# Digital_Clock_v2.net
KiCad netlist of a schematic drawn in EAGLE
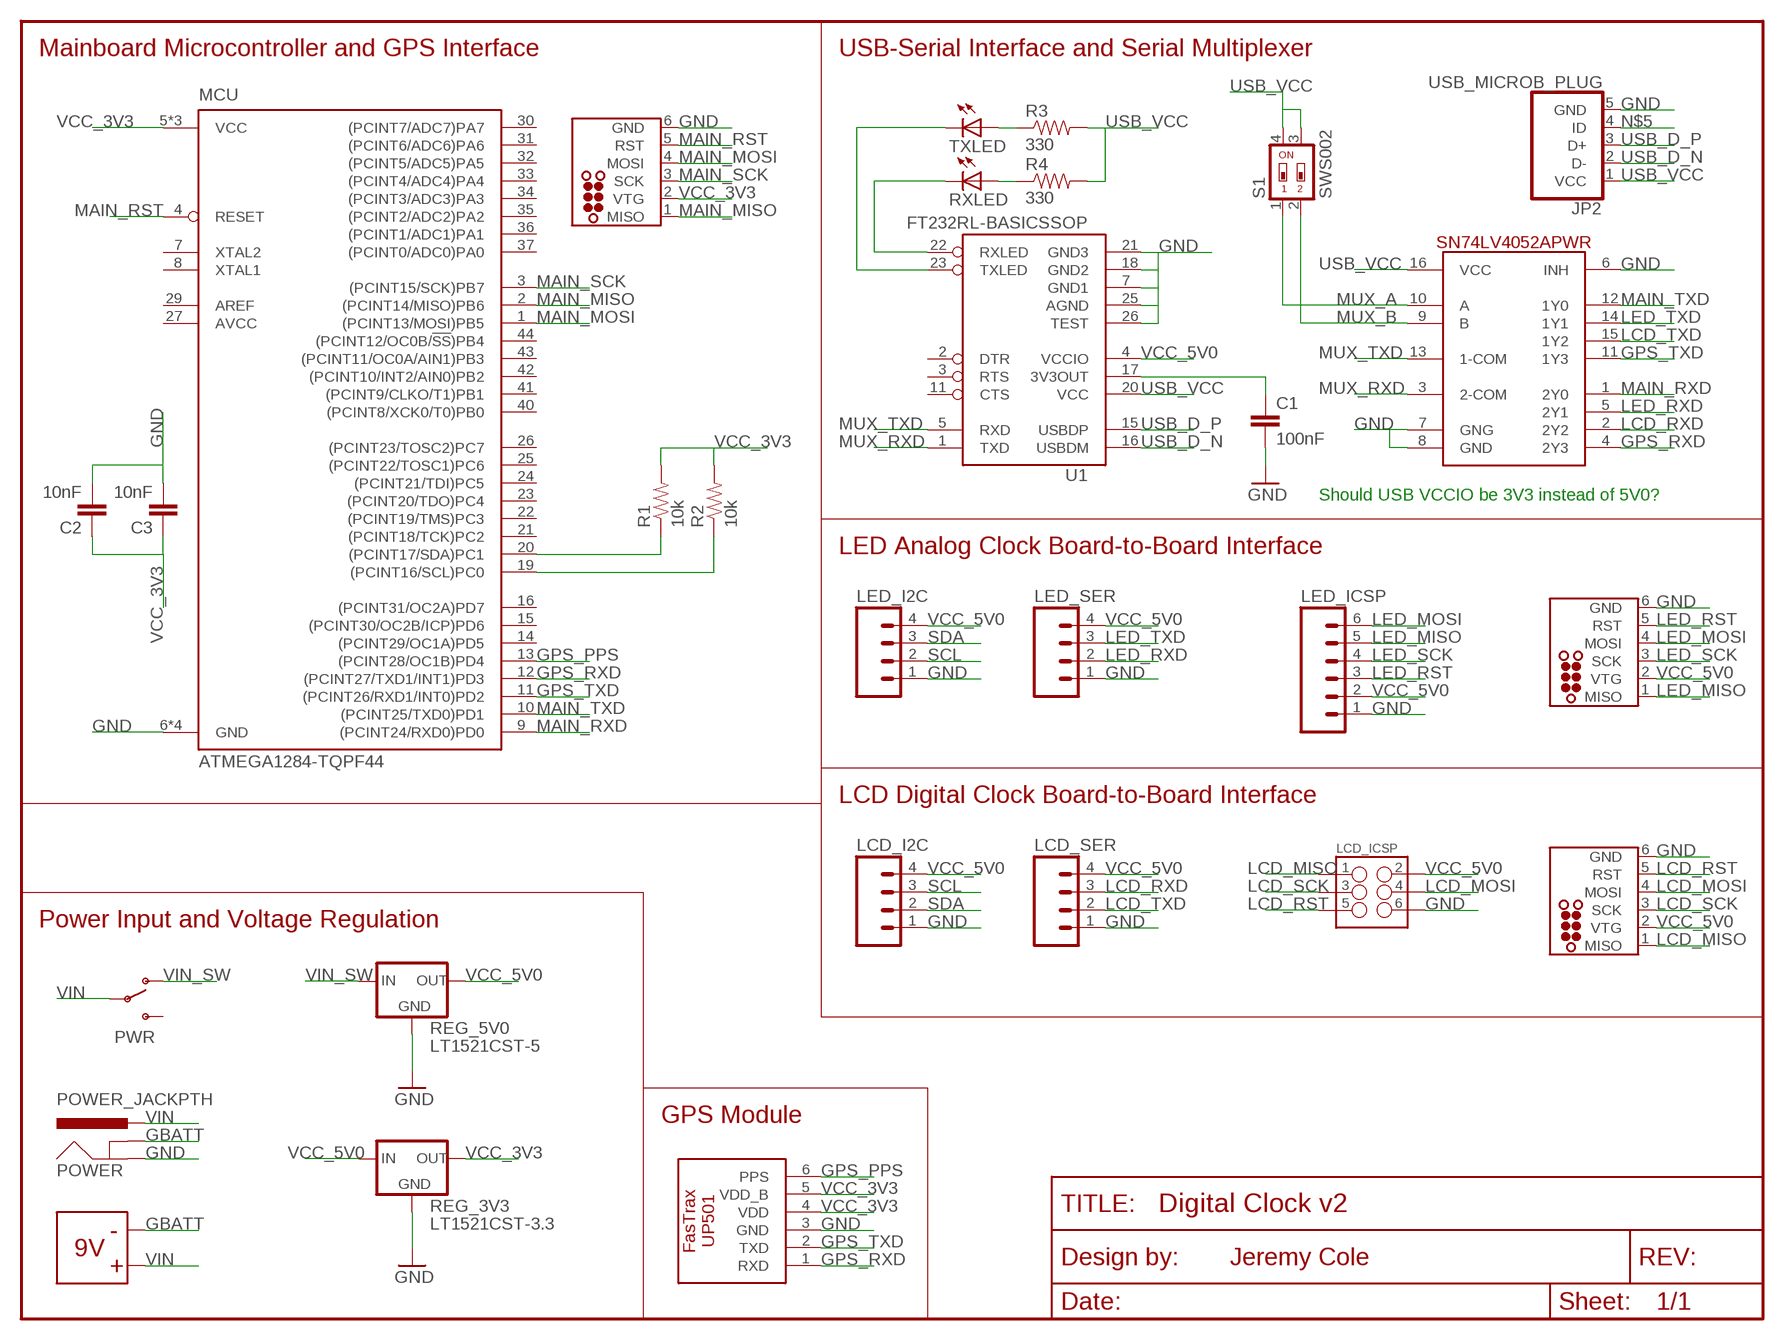
[diagram p0: schematic, sheet 1]

(export (version "E")
  (design (tool "Eeschema 10.0.6"))
  (components
    (comp (ref "9V_BATTERY")
      (value "BATTERY-BH9VGLUE")
      (footprint "eagle-import:BATTERY-BH9V-GLUE")
      (libsource (lib "eagle-import") (part "BATTERY-BH9VGLUE"))
    )
    (comp (ref "C1")
      (value "100nF")
      (footprint "eagle-import:0603-CAP")
      (libsource (lib "eagle-import") (part "CAP-0603"))
    )
    (comp (ref "C2")
      (value "10nF")
      (footprint "eagle-import:0603-CAP")
      (libsource (lib "eagle-import") (part "CAP-0603"))
    )
    (comp (ref "C3")
      (value "10nF")
      (footprint "eagle-import:0603-CAP")
      (libsource (lib "eagle-import") (part "CAP-0603"))
    )
    (comp (ref "FRAME1")
      (value "FRAME-LETTERNO_PACKAGE")
      (footprint "eagle-import:DUMMY")
      (fields (field (name "DESIGNER") "Nobody"))
      (libsource (lib "eagle-import") (part "FRAME-LETTERNO_PACKAGE"))
    )
    (comp (ref "GPS_ICSP_TC")
      (value "TC2030-AVR-NL")
      (footprint "eagle-import:TC2030-NL")
      (libsource (lib "eagle-import") (part "TC2030-AVR-NL"))
    )
    (comp (ref "JP2")
      (value "USB_MICROB_PLUG")
      (footprint "eagle-import:USB_MICRO_B_TYCO")
      (libsource (lib "eagle-import") (part "USB_MICROB_PLUG"))
    )
    (comp (ref "LCD_I2C")
      (value "M04LONGPADS")
      (footprint "eagle-import:1X04_LONGPADS")
      (libsource (lib "eagle-import") (part "M04LONGPADS"))
    )
    (comp (ref "LCD_ICSP")
      (value "M03X22X3_SILK_MALE_PTH")
      (footprint "eagle-import:2X3")
      (libsource (lib "eagle-import") (part "M03X22X3_SILK_MALE_PTH"))
    )
    (comp (ref "LCD_ICSP_TC")
      (value "TC2030-AVR-NL")
      (footprint "eagle-import:TC2030-NL")
      (libsource (lib "eagle-import") (part "TC2030-AVR-NL"))
    )
    (comp (ref "LCD_SER")
      (value "M04LONGPADS")
      (footprint "eagle-import:1X04_LONGPADS")
      (libsource (lib "eagle-import") (part "M04LONGPADS"))
    )
    (comp (ref "LED_I2C")
      (value "M04LONGPADS")
      (footprint "eagle-import:1X04_LONGPADS")
      (libsource (lib "eagle-import") (part "M04LONGPADS"))
    )
    (comp (ref "LED_ICSP")
      (value "M06LONGPADS")
      (footprint "eagle-import:1X06_LONGPADS")
      (libsource (lib "eagle-import") (part "M06LONGPADS"))
    )
    (comp (ref "LED_ICSP_TC")
      (value "TC2030-AVR-NL")
      (footprint "eagle-import:TC2030-NL")
      (libsource (lib "eagle-import") (part "TC2030-AVR-NL"))
    )
    (comp (ref "LED_SER")
      (value "M04LONGPADS")
      (footprint "eagle-import:1X04_LONGPADS")
      (libsource (lib "eagle-import") (part "M04LONGPADS"))
    )
    (comp (ref "MCU")
      (value "ATMEGA1284-TQPF44")
      (footprint "eagle-import:TQFP44")
      (libsource (lib "eagle-import") (part "ATMEGA1284-TQPF44"))
    )
    (comp (ref "POWER")
      (value "POWER_JACKPTH")
      (footprint "eagle-import:POWER_JACK_PTH")
      (libsource (lib "eagle-import") (part "POWER_JACKPTH"))
    )
    (comp (ref "PWR")
      (value "SWITCH-SPSTPTH")
      (footprint "eagle-import:SWITCH-SPDT")
      (libsource (lib "eagle-import") (part "SWITCH-SPSTPTH"))
    )
    (comp (ref "R1")
      (value "10k")
      (footprint "eagle-import:0603")
      (libsource (lib "eagle-import") (part "RESISTOR-0603"))
    )
    (comp (ref "R2")
      (value "10k")
      (footprint "eagle-import:0603")
      (libsource (lib "eagle-import") (part "RESISTOR-0603"))
    )
    (comp (ref "R3")
      (value "330")
      (footprint "eagle-import:0603")
      (libsource (lib "eagle-import") (part "RESISTOR-0603"))
    )
    (comp (ref "R4")
      (value "330")
      (footprint "eagle-import:0603")
      (libsource (lib "eagle-import") (part "RESISTOR-0603"))
    )
    (comp (ref "REG_3V3")
      (value "LT1521CST-3.3")
      (footprint "eagle-import:SOT223")
      (libsource (lib "eagle-import") (part "LT1521"))
    )
    (comp (ref "REG_5V0")
      (value "LT1521CST-5")
      (footprint "eagle-import:SOT223")
      (libsource (lib "eagle-import") (part "LT1521"))
    )
    (comp (ref "RXLED")
      (value "LED-0603")
      (footprint "eagle-import:0603-LED")
      (libsource (lib "eagle-import") (part "LED-0603"))
    )
    (comp (ref "S1")
      (value "SWS002")
      (footprint "eagle-import:SMS-002")
      (libsource (lib "eagle-import") (part "SWS002"))
    )
    (comp (ref "TXLED")
      (value "LED-0603")
      (footprint "eagle-import:0603-LED")
      (libsource (lib "eagle-import") (part "LED-0603"))
    )
    (comp (ref "U$15")
      (value "FASTRAX-UP501")
      (footprint "eagle-import:FASTRAX-UP501")
      (libsource (lib "eagle-import") (part "FASTRAX-UP501"))
    )
    (comp (ref "U$16")
      (value "SV74LV4052APWR")
      (footprint "eagle-import:TSSOP16")
      (libsource (lib "eagle-import") (part "SV74LV4052APWR"))
    )
    (comp (ref "U1")
      (value "FT232RL-BASICSSOP")
      (footprint "eagle-import:SSOP28DB")
      (libsource (lib "eagle-import") (part "FT232RL-BASICSSOP"))
    )
  )
  (nets
    (net (code "1") (name "/AVCC") (class "Default")
      (node (ref "MCU") (pin "27") (pinfunction "AVCC_27") (pintype "power_in"))
    )
    (net (code "2") (name "/GBATT") (class "Default")
      (node (ref "9V_BATTERY") (pin "9V-") (pinfunction "9V-_9V-") (pintype "power_in"))
      (node (ref "POWER") (pin "GNDBREAK") (pinfunction "GNDBREAK_GNDBREAK") (pintype "bidirectional"))
    )
    (net (code "3") (name "/GPS_PPS") (class "Default")
      (node (ref "MCU") (pin "13") (pinfunction "(PCINT28/OC1B)PD4_13") (pintype "bidirectional"))
      (node (ref "U$15") (pin "6") (pinfunction "PPS_6") (pintype "output"))
    )
    (net (code "4") (name "/GPS_RXD") (class "Default")
      (node (ref "MCU") (pin "12") (pinfunction "(PCINT27/TXD1/INT1)PD3_12") (pintype "bidirectional"))
      (node (ref "U$15") (pin "1") (pinfunction "RXD_1") (pintype "input"))
      (node (ref "U$16") (pin "4") (pinfunction "2Y3_4") (pintype "bidirectional"))
    )
    (net (code "5") (name "/GPS_TXD") (class "Default")
      (node (ref "MCU") (pin "11") (pinfunction "(PCINT26/RXD1/INT0)PD2_11") (pintype "bidirectional"))
      (node (ref "U$15") (pin "2") (pinfunction "TXD_2") (pintype "output"))
      (node (ref "U$16") (pin "11") (pinfunction "1Y3_11") (pintype "bidirectional"))
    )
    (net (code "6") (name "/LCD_MISO") (class "Default")
      (node (ref "LCD_ICSP") (pin "1") (pinfunction "1_1") (pintype "bidirectional"))
      (node (ref "LCD_ICSP_TC") (pin "1") (pinfunction "MISO_1") (pintype "passive"))
    )
    (net (code "7") (name "/LCD_MOSI") (class "Default")
      (node (ref "LCD_ICSP") (pin "4") (pinfunction "4_4") (pintype "bidirectional"))
      (node (ref "LCD_ICSP_TC") (pin "4") (pinfunction "MOSI_4") (pintype "bidirectional"))
    )
    (net (code "8") (name "/LCD_RST") (class "Default")
      (node (ref "LCD_ICSP") (pin "5") (pinfunction "5_5") (pintype "bidirectional"))
      (node (ref "LCD_ICSP_TC") (pin "5") (pinfunction "RST_5") (pintype "output"))
    )
    (net (code "9") (name "/LCD_RXD") (class "Default")
      (node (ref "LCD_SER") (pin "3") (pinfunction "3_3") (pintype "passive"))
      (node (ref "U$16") (pin "2") (pinfunction "2Y2_2") (pintype "bidirectional"))
    )
    (net (code "10") (name "/LCD_SCK") (class "Default")
      (node (ref "LCD_ICSP") (pin "3") (pinfunction "3_3") (pintype "bidirectional"))
      (node (ref "LCD_ICSP_TC") (pin "3") (pinfunction "SCK_3") (pintype "power_in"))
    )
    (net (code "11") (name "/LCD_TXD") (class "Default")
      (node (ref "LCD_SER") (pin "2") (pinfunction "2_2") (pintype "passive"))
      (node (ref "U$16") (pin "15") (pinfunction "1Y2_15") (pintype "bidirectional"))
    )
    (net (code "12") (name "/LED_MISO") (class "Default")
      (node (ref "LED_ICSP") (pin "5") (pinfunction "5_5") (pintype "passive"))
      (node (ref "LED_ICSP_TC") (pin "1") (pinfunction "MISO_1") (pintype "passive"))
    )
    (net (code "13") (name "/LED_MOSI") (class "Default")
      (node (ref "LED_ICSP") (pin "6") (pinfunction "6_6") (pintype "passive"))
      (node (ref "LED_ICSP_TC") (pin "4") (pinfunction "MOSI_4") (pintype "bidirectional"))
    )
    (net (code "14") (name "/LED_RST") (class "Default")
      (node (ref "LED_ICSP") (pin "3") (pinfunction "3_3") (pintype "passive"))
      (node (ref "LED_ICSP_TC") (pin "5") (pinfunction "RST_5") (pintype "output"))
    )
    (net (code "15") (name "/LED_RXD") (class "Default")
      (node (ref "LED_SER") (pin "2") (pinfunction "2_2") (pintype "passive"))
      (node (ref "U$16") (pin "5") (pinfunction "2Y1_5") (pintype "bidirectional"))
    )
    (net (code "16") (name "/LED_SCK") (class "Default")
      (node (ref "LED_ICSP") (pin "4") (pinfunction "4_4") (pintype "passive"))
      (node (ref "LED_ICSP_TC") (pin "3") (pinfunction "SCK_3") (pintype "power_in"))
    )
    (net (code "17") (name "/LED_TXD") (class "Default")
      (node (ref "LED_SER") (pin "3") (pinfunction "3_3") (pintype "passive"))
      (node (ref "U$16") (pin "14") (pinfunction "1Y1_14") (pintype "bidirectional"))
    )
    (net (code "18") (name "/MAIN_MISO") (class "Default")
      (node (ref "GPS_ICSP_TC") (pin "1") (pinfunction "MISO_1") (pintype "passive"))
      (node (ref "MCU") (pin "2") (pinfunction "(PCINT14/MISO)PB6_2") (pintype "bidirectional"))
    )
    (net (code "19") (name "/MAIN_MOSI") (class "Default")
      (node (ref "GPS_ICSP_TC") (pin "4") (pinfunction "MOSI_4") (pintype "bidirectional"))
      (node (ref "MCU") (pin "1") (pinfunction "(PCINT13/MOSI)PB5_1") (pintype "bidirectional"))
    )
    (net (code "20") (name "/MAIN_RST") (class "Default")
      (node (ref "GPS_ICSP_TC") (pin "5") (pinfunction "RST_5") (pintype "output"))
      (node (ref "MCU") (pin "4") (pinfunction "RESET_4") (pintype "input"))
    )
    (net (code "21") (name "/MAIN_RXD") (class "Default")
      (node (ref "MCU") (pin "9") (pinfunction "(PCINT24/RXD0)PD0_9") (pintype "bidirectional"))
      (node (ref "U$16") (pin "1") (pinfunction "2Y0_1") (pintype "bidirectional"))
    )
    (net (code "22") (name "/MAIN_SCK") (class "Default")
      (node (ref "GPS_ICSP_TC") (pin "3") (pinfunction "SCK_3") (pintype "power_in"))
      (node (ref "MCU") (pin "3") (pinfunction "(PCINT15/SCK)PB7_3") (pintype "bidirectional"))
    )
    (net (code "23") (name "/MAIN_TXD") (class "Default")
      (node (ref "MCU") (pin "10") (pinfunction "(PCINT25/TXD0)PD1_10") (pintype "bidirectional"))
      (node (ref "U$16") (pin "12") (pinfunction "1Y0_12") (pintype "bidirectional"))
    )
    (net (code "24") (name "/MUX_A") (class "Default")
      (node (ref "S1") (pin "1") (pinfunction "1_1") (pintype "passive"))
      (node (ref "U$16") (pin "10") (pinfunction "A_10") (pintype "bidirectional"))
    )
    (net (code "25") (name "/MUX_B") (class "Default")
      (node (ref "S1") (pin "2") (pinfunction "2_2") (pintype "passive"))
      (node (ref "U$16") (pin "9") (pinfunction "B_9") (pintype "bidirectional"))
    )
    (net (code "26") (name "/MUX_RXD") (class "Default")
      (node (ref "U$16") (pin "3") (pinfunction "2-COM_3") (pintype "bidirectional"))
      (node (ref "U1") (pin "1") (pinfunction "TXD_1") (pintype "output"))
    )
    (net (code "27") (name "/MUX_TXD") (class "Default")
      (node (ref "U$16") (pin "13") (pinfunction "1-COM_13") (pintype "bidirectional"))
      (node (ref "U1") (pin "5") (pinfunction "RXD_5") (pintype "input"))
    )
    (net (code "28") (name "/N$5") (class "Default")
      (node (ref "JP2") (pin "4") (pinfunction "ID_4") (pintype "bidirectional"))
    )
    (net (code "29") (name "/SCL") (class "Default")
      (node (ref "LCD_I2C") (pin "3") (pinfunction "3_3") (pintype "passive"))
      (node (ref "LED_I2C") (pin "2") (pinfunction "2_2") (pintype "passive"))
      (node (ref "MCU") (pin "19") (pinfunction "(PCINT16/SCL)PC0_19") (pintype "output"))
      (node (ref "R2") (pin "1") (pinfunction "1_1") (pintype "passive"))
    )
    (net (code "30") (name "/SDA") (class "Default")
      (node (ref "LCD_I2C") (pin "2") (pinfunction "2_2") (pintype "passive"))
      (node (ref "LED_I2C") (pin "3") (pinfunction "3_3") (pintype "passive"))
      (node (ref "MCU") (pin "20") (pinfunction "(PCINT17/SDA)PC1_20") (pintype "output"))
      (node (ref "R1") (pin "1") (pinfunction "1_1") (pintype "passive"))
    )
    (net (code "31") (name "/USB_D_N") (class "Default")
      (node (ref "JP2") (pin "2") (pinfunction "D-_2") (pintype "bidirectional"))
      (node (ref "U1") (pin "16") (pinfunction "USBDM_16") (pintype "bidirectional"))
    )
    (net (code "32") (name "/USB_D_P") (class "Default")
      (node (ref "JP2") (pin "3") (pinfunction "D+_3") (pintype "bidirectional"))
      (node (ref "U1") (pin "15") (pinfunction "USBDP_15") (pintype "bidirectional"))
    )
    (net (code "33") (name "/USB_VCC") (class "Default")
      (node (ref "JP2") (pin "1") (pinfunction "VCC_1") (pintype "bidirectional"))
      (node (ref "R3") (pin "2") (pinfunction "2_2") (pintype "passive"))
      (node (ref "R4") (pin "2") (pinfunction "2_2") (pintype "passive"))
      (node (ref "S1") (pin "3") (pinfunction "3_3") (pintype "passive"))
      (node (ref "S1") (pin "4") (pinfunction "4_4") (pintype "passive"))
      (node (ref "U$16") (pin "16") (pinfunction "VCC_16") (pintype "bidirectional"))
      (node (ref "U1") (pin "20") (pinfunction "VCC_20") (pintype "power_in"))
    )
    (net (code "34") (name "/VCC_3V3") (class "Default")
      (node (ref "C2") (pin "1") (pinfunction "1_1") (pintype "passive"))
      (node (ref "C3") (pin "1") (pinfunction "1_1") (pintype "passive"))
      (node (ref "GPS_ICSP_TC") (pin "2") (pinfunction "VTG_2") (pintype "power_in"))
      (node (ref "MCU") (pin "17") (pinfunction "VCC_17") (pintype "power_in"))
      (node (ref "MCU") (pin "38") (pinfunction "VCC_38") (pintype "power_in"))
      (node (ref "MCU") (pin "5") (pinfunction "VCC_5") (pintype "power_in"))
      (node (ref "R1") (pin "2") (pinfunction "2_2") (pintype "passive"))
      (node (ref "R2") (pin "2") (pinfunction "2_2") (pintype "passive"))
      (node (ref "REG_3V3") (pin "3") (pinfunction "OUT_3") (pintype "passive"))
      (node (ref "U$15") (pin "4") (pinfunction "VDD_4") (pintype "power_in"))
      (node (ref "U$15") (pin "5") (pinfunction "VDD_B_5") (pintype "power_in"))
    )
    (net (code "35") (name "/VCC_5V0") (class "Default")
      (node (ref "LCD_I2C") (pin "4") (pinfunction "4_4") (pintype "passive"))
      (node (ref "LCD_ICSP") (pin "2") (pinfunction "2_2") (pintype "bidirectional"))
      (node (ref "LCD_ICSP_TC") (pin "2") (pinfunction "VTG_2") (pintype "power_in"))
      (node (ref "LCD_SER") (pin "4") (pinfunction "4_4") (pintype "passive"))
      (node (ref "LED_I2C") (pin "4") (pinfunction "4_4") (pintype "passive"))
      (node (ref "LED_ICSP") (pin "2") (pinfunction "2_2") (pintype "passive"))
      (node (ref "LED_ICSP_TC") (pin "2") (pinfunction "VTG_2") (pintype "power_in"))
      (node (ref "LED_SER") (pin "4") (pinfunction "4_4") (pintype "passive"))
      (node (ref "REG_3V3") (pin "1") (pinfunction "IN_1") (pintype "input"))
      (node (ref "REG_5V0") (pin "3") (pinfunction "OUT_3") (pintype "passive"))
      (node (ref "U1") (pin "4") (pinfunction "VCCIO_4") (pintype "power_in"))
    )
    (net (code "36") (name "/VIN") (class "Default")
      (node (ref "9V_BATTERY") (pin "9V+") (pinfunction "9V+_9V+") (pintype "power_in"))
      (node (ref "POWER") (pin "PWR") (pinfunction "PWR_PWR") (pintype "bidirectional"))
      (node (ref "PWR") (pin "2") (pinfunction "P_2") (pintype "passive"))
    )
    (net (code "37") (name "/VIN_SW") (class "Default")
      (node (ref "PWR") (pin "1") (pinfunction "O_1") (pintype "passive"))
      (node (ref "REG_5V0") (pin "1") (pinfunction "IN_1") (pintype "input"))
    )
    (net (code "38") (name "GND") (class "Default")
      (node (ref "C1") (pin "2") (pinfunction "2_2") (pintype "passive"))
      (node (ref "C2") (pin "2") (pinfunction "2_2") (pintype "passive"))
      (node (ref "C3") (pin "2") (pinfunction "2_2") (pintype "passive"))
      (node (ref "GPS_ICSP_TC") (pin "6") (pinfunction "GND_6") (pintype "bidirectional"))
      (node (ref "JP2") (pin "5") (pinfunction "GND_5") (pintype "bidirectional"))
      (node (ref "LCD_I2C") (pin "1") (pinfunction "1_1") (pintype "passive"))
      (node (ref "LCD_ICSP") (pin "6") (pinfunction "6_6") (pintype "bidirectional"))
      (node (ref "LCD_ICSP_TC") (pin "6") (pinfunction "GND_6") (pintype "bidirectional"))
      (node (ref "LCD_SER") (pin "1") (pinfunction "1_1") (pintype "passive"))
      (node (ref "LED_I2C") (pin "1") (pinfunction "1_1") (pintype "passive"))
      (node (ref "LED_ICSP") (pin "1") (pinfunction "1_1") (pintype "passive"))
      (node (ref "LED_ICSP_TC") (pin "6") (pinfunction "GND_6") (pintype "bidirectional"))
      (node (ref "LED_SER") (pin "1") (pinfunction "1_1") (pintype "passive"))
      (node (ref "MCU") (pin "18") (pinfunction "GND_18") (pintype "power_in"))
      (node (ref "MCU") (pin "28") (pinfunction "GND_28") (pintype "power_in"))
      (node (ref "MCU") (pin "39") (pinfunction "GND_39") (pintype "power_in"))
      (node (ref "MCU") (pin "6") (pinfunction "GND_6") (pintype "power_in"))
      (node (ref "POWER") (pin "GND") (pinfunction "GND_GND") (pintype "bidirectional"))
      (node (ref "REG_3V3") (pin "2") (pinfunction "GND_2") (pintype "input"))
      (node (ref "REG_3V3") (pin "TAB") (pinfunction "GND_TAB") (pintype "input"))
      (node (ref "REG_5V0") (pin "2") (pinfunction "GND_2") (pintype "input"))
      (node (ref "REG_5V0") (pin "TAB") (pinfunction "GND_TAB") (pintype "input"))
      (node (ref "U$15") (pin "3") (pinfunction "GND_3") (pintype "power_in"))
      (node (ref "U$16") (pin "6") (pinfunction "INH_6") (pintype "bidirectional"))
      (node (ref "U$16") (pin "7") (pinfunction "GNG_7") (pintype "bidirectional"))
      (node (ref "U$16") (pin "8") (pinfunction "GND_8") (pintype "bidirectional"))
      (node (ref "U1") (pin "18") (pinfunction "GND2_18") (pintype "power_in"))
      (node (ref "U1") (pin "21") (pinfunction "GND3_21") (pintype "power_in"))
      (node (ref "U1") (pin "25") (pinfunction "AGND_25") (pintype "power_in"))
      (node (ref "U1") (pin "26") (pinfunction "TEST_26") (pintype "input"))
      (node (ref "U1") (pin "7") (pinfunction "GND1_7") (pintype "power_in"))
    )
    (net (code "39") (name "Net-(R3-Pad1)") (class "Default")
      (node (ref "R3") (pin "1") (pinfunction "1_1") (pintype "passive"))
      (node (ref "TXLED") (pin "A") (pinfunction "A_A") (pintype "passive"))
    )
    (net (code "40") (name "Net-(R4-Pad1)") (class "Default")
      (node (ref "R4") (pin "1") (pinfunction "1_1") (pintype "passive"))
      (node (ref "RXLED") (pin "A") (pinfunction "A_A") (pintype "passive"))
    )
    (net (code "41") (name "Net-(U1-3V3OUT)") (class "Default")
      (node (ref "C1") (pin "1") (pinfunction "1_1") (pintype "passive"))
      (node (ref "U1") (pin "17") (pinfunction "3V3OUT_17") (pintype "output"))
    )
    (net (code "42") (name "Net-(U1-RXLED)") (class "Default")
      (node (ref "RXLED") (pin "C") (pinfunction "C_C") (pintype "passive"))
      (node (ref "U1") (pin "22") (pinfunction "RXLED_22") (pintype "bidirectional"))
    )
    (net (code "43") (name "Net-(U1-TXLED)") (class "Default")
      (node (ref "TXLED") (pin "C") (pinfunction "C_C") (pintype "passive"))
      (node (ref "U1") (pin "23") (pinfunction "TXLED_23") (pintype "bidirectional"))
    )
    (net (code "44") (name "unconnected-(MCU-(PCINT0{slash}ADC0)PA0-Pad37)") (class "Default")
      (node (ref "MCU") (pin "37") (pinfunction "(PCINT0/ADC0)PA0_37") (pintype "bidirectional"))
    )
    (net (code "45") (name "unconnected-(MCU-(PCINT1{slash}ADC1)PA1-Pad36)") (class "Default")
      (node (ref "MCU") (pin "36") (pinfunction "(PCINT1/ADC1)PA1_36") (pintype "bidirectional"))
    )
    (net (code "46") (name "unconnected-(MCU-(PCINT2{slash}ADC2)PA2-Pad35)") (class "Default")
      (node (ref "MCU") (pin "35") (pinfunction "(PCINT2/ADC2)PA2_35") (pintype "bidirectional"))
    )
    (net (code "47") (name "unconnected-(MCU-(PCINT3{slash}ADC3)PA3-Pad34)") (class "Default")
      (node (ref "MCU") (pin "34") (pinfunction "(PCINT3/ADC3)PA3_34") (pintype "bidirectional"))
    )
    (net (code "48") (name "unconnected-(MCU-(PCINT4{slash}ADC4)PA4-Pad33)") (class "Default")
      (node (ref "MCU") (pin "33") (pinfunction "(PCINT4/ADC4)PA4_33") (pintype "bidirectional"))
    )
    (net (code "49") (name "unconnected-(MCU-(PCINT5{slash}ADC5)PA5-Pad32)") (class "Default")
      (node (ref "MCU") (pin "32") (pinfunction "(PCINT5/ADC5)PA5_32") (pintype "bidirectional"))
    )
    (net (code "50") (name "unconnected-(MCU-(PCINT6{slash}ADC6)PA6-Pad31)") (class "Default")
      (node (ref "MCU") (pin "31") (pinfunction "(PCINT6/ADC6)PA6_31") (pintype "bidirectional"))
    )
    (net (code "51") (name "unconnected-(MCU-(PCINT7{slash}ADC7)PA7-Pad30)") (class "Default")
      (node (ref "MCU") (pin "30") (pinfunction "(PCINT7/ADC7)PA7_30") (pintype "bidirectional"))
    )
    (net (code "52") (name "unconnected-(MCU-(PCINT8{slash}XCK0{slash}T0)PB0-Pad40)") (class "Default")
      (node (ref "MCU") (pin "40") (pinfunction "(PCINT8/XCK0/T0)PB0_40") (pintype "bidirectional"))
    )
    (net (code "53") (name "unconnected-(MCU-(PCINT9{slash}CLKO{slash}T1)PB1-Pad41)") (class "Default")
      (node (ref "MCU") (pin "41") (pinfunction "(PCINT9/CLKO/T1)PB1_41") (pintype "bidirectional"))
    )
    (net (code "54") (name "unconnected-(MCU-(PCINT10{slash}INT2{slash}AIN0)PB2-Pad42)") (class "Default")
      (node (ref "MCU") (pin "42") (pinfunction "(PCINT10/INT2/AIN0)PB2_42") (pintype "bidirectional"))
    )
    (net (code "55") (name "unconnected-(MCU-(PCINT11{slash}OC0A{slash}AIN1)PB3-Pad43)") (class "Default")
      (node (ref "MCU") (pin "43") (pinfunction "(PCINT11/OC0A/AIN1)PB3_43") (pintype "bidirectional"))
    )
    (net (code "56") (name "unconnected-(MCU-(PCINT12{slash}OC0B{slash}~{SS})PB4-Pad44)") (class "Default")
      (node (ref "MCU") (pin "44") (pinfunction "(PCINT12/OC0B/~{SS})PB4_44") (pintype "bidirectional"))
    )
    (net (code "57") (name "unconnected-(MCU-(PCINT18{slash}TCK)PC2-Pad21)") (class "Default")
      (node (ref "MCU") (pin "21") (pinfunction "(PCINT18/TCK)PC2_21") (pintype "output"))
    )
    (net (code "58") (name "unconnected-(MCU-(PCINT19{slash}TMS)PC3-Pad22)") (class "Default")
      (node (ref "MCU") (pin "22") (pinfunction "(PCINT19/TMS)PC3_22") (pintype "output"))
    )
    (net (code "59") (name "unconnected-(MCU-(PCINT20{slash}TDO)PC4-Pad23)") (class "Default")
      (node (ref "MCU") (pin "23") (pinfunction "(PCINT20/TDO)PC4_23") (pintype "output"))
    )
    (net (code "60") (name "unconnected-(MCU-(PCINT21{slash}TDI)PC5-Pad24)") (class "Default")
      (node (ref "MCU") (pin "24") (pinfunction "(PCINT21/TDI)PC5_24") (pintype "output"))
    )
    (net (code "61") (name "unconnected-(MCU-(PCINT22{slash}TOSC1)PC6-Pad25)") (class "Default")
      (node (ref "MCU") (pin "25") (pinfunction "(PCINT22/TOSC1)PC6_25") (pintype "output"))
    )
    (net (code "62") (name "unconnected-(MCU-(PCINT23{slash}TOSC2)PC7-Pad26)") (class "Default")
      (node (ref "MCU") (pin "26") (pinfunction "(PCINT23/TOSC2)PC7_26") (pintype "output"))
    )
    (net (code "63") (name "unconnected-(MCU-(PCINT29{slash}OC1A)PD5-Pad14)") (class "Default")
      (node (ref "MCU") (pin "14") (pinfunction "(PCINT29/OC1A)PD5_14") (pintype "bidirectional"))
    )
    (net (code "64") (name "unconnected-(MCU-(PCINT30{slash}OC2B{slash}ICP)PD6-Pad15)") (class "Default")
      (node (ref "MCU") (pin "15") (pinfunction "(PCINT30/OC2B/ICP)PD6_15") (pintype "bidirectional"))
    )
    (net (code "65") (name "unconnected-(MCU-(PCINT31{slash}OC2A)PD7-Pad16)") (class "Default")
      (node (ref "MCU") (pin "16") (pinfunction "(PCINT31/OC2A)PD7_16") (pintype "bidirectional"))
    )
    (net (code "66") (name "unconnected-(MCU-AREF-Pad29)") (class "Default")
      (node (ref "MCU") (pin "29") (pinfunction "AREF_29") (pintype "passive"))
    )
    (net (code "67") (name "unconnected-(MCU-XTAL1-Pad8)") (class "Default")
      (node (ref "MCU") (pin "8") (pinfunction "XTAL1_8") (pintype "bidirectional"))
    )
    (net (code "68") (name "unconnected-(MCU-XTAL2-Pad7)") (class "Default")
      (node (ref "MCU") (pin "7") (pinfunction "XTAL2_7") (pintype "bidirectional"))
    )
    (net (code "69") (name "unconnected-(PWR-S-Pad3)") (class "Default")
      (node (ref "PWR") (pin "3") (pinfunction "S_3") (pintype "passive"))
    )
    (net (code "70") (name "unconnected-(U1-CTS-Pad11)") (class "Default")
      (node (ref "U1") (pin "11") (pinfunction "CTS_11") (pintype "bidirectional"))
    )
    (net (code "71") (name "unconnected-(U1-DTR-Pad2)") (class "Default")
      (node (ref "U1") (pin "2") (pinfunction "DTR_2") (pintype "bidirectional"))
    )
    (net (code "72") (name "unconnected-(U1-RTS-Pad3)") (class "Default")
      (node (ref "U1") (pin "3") (pinfunction "RTS_3") (pintype "bidirectional"))
    )
  )
)
